# Mainboard.net
KiCad netlist of a schematic drawn in Altium Designer
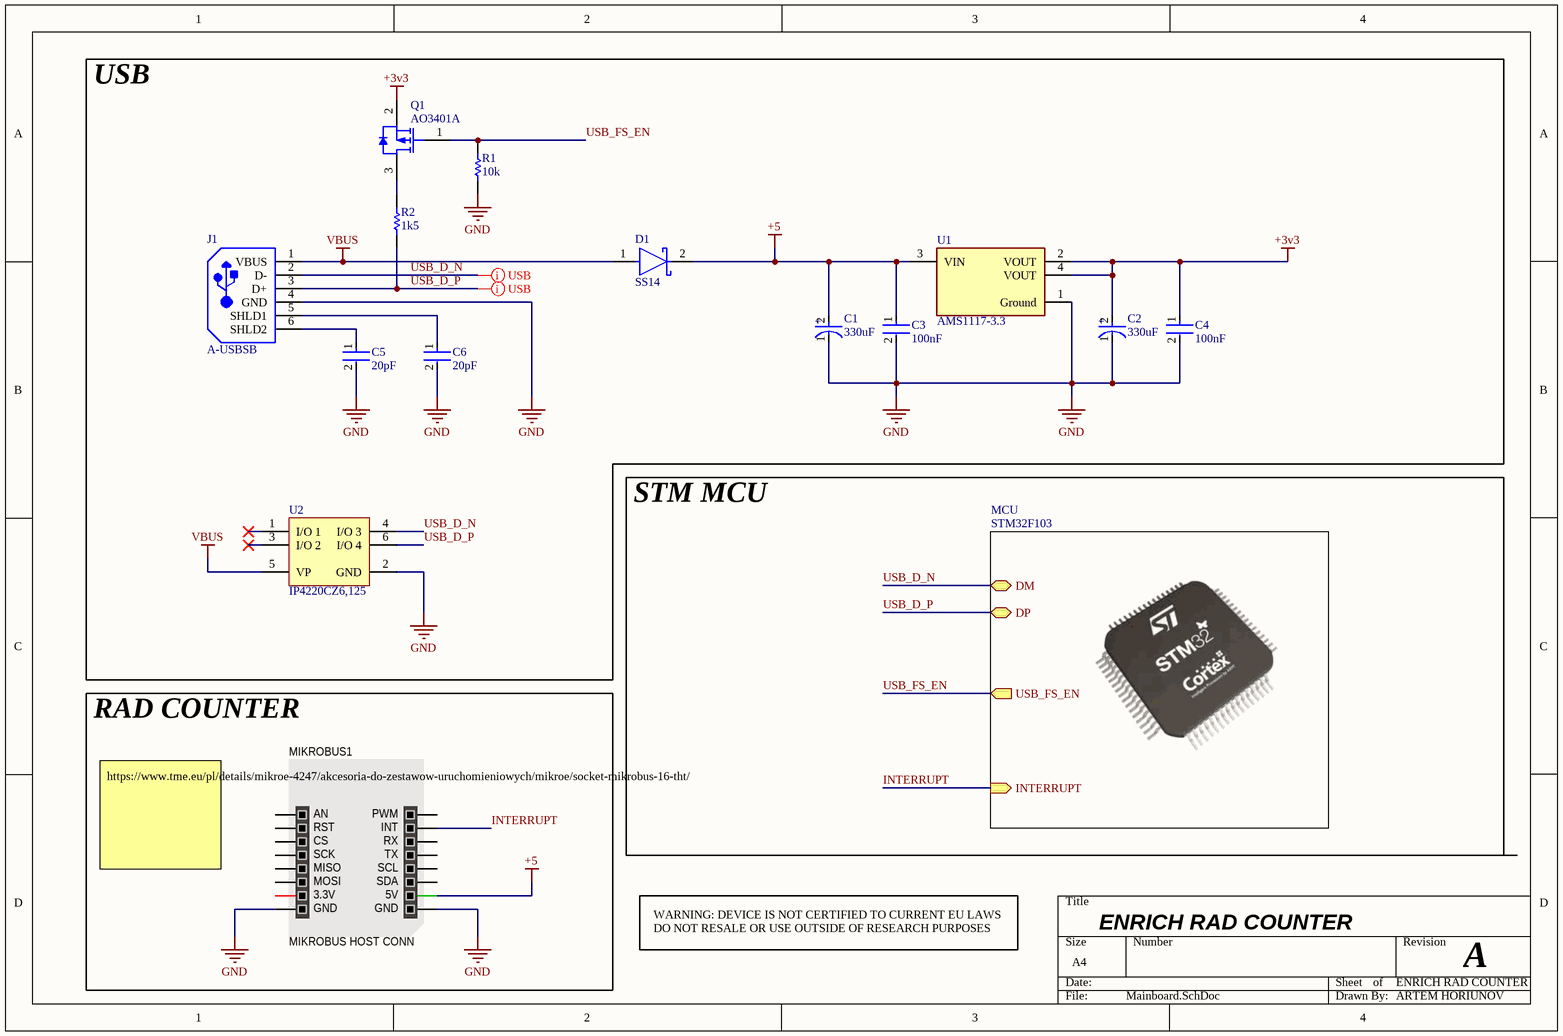
[diagram p0: Mainboard.SchDoc]

(export (version "E")
  (design (tool "Eeschema 10.0.6"))
  (components
    (comp (ref "C1")
      (value "330uF")
      (footprint "FP-OS-CON-SMT-F12-MFG")
      (description "Conductive Polymer Aluminum Solid Capacitors (OS-CON) 330uF ±20% 16V RADIAL SMT 10x12.6mm")
      (fields (field (name "TOLERANCE") "20%") (field (name "VOLTAGE") "16V"))
      (libsource (lib "Altium Content Vault") (part "a7907c86e72a156c28511143de7831b"))
    )
    (comp (ref "C2")
      (value "330uF")
      (footprint "FP-OS-CON-SMT-F12-MFG")
      (description "Conductive Polymer Aluminum Solid Capacitors (OS-CON) 330uF ±20% 16V RADIAL SMT 10x12.6mm")
      (fields (field (name "TOLERANCE") "20%") (field (name "VOLTAGE") "16V"))
      (libsource (lib "Altium Content Vault") (part "a7907c86e72a156c28511143de7831b"))
    )
    (comp (ref "C3")
      (value "100nF")
      (footprint "FP-C0402-BB-MFG")
      (description "CAP CER 0.1UF 10V X5R 0402")
      (fields (field (name "MANUFACTURER") "Kemet") (field (name "TOLERANCE") "0.1"))
      (libsource (lib "Altium Content Vault") (part "b4654b650e69147ec39a6b967a45e02"))
    )
    (comp (ref "C4")
      (value "100nF")
      (footprint "FP-C0402-BB-MFG")
      (description "CAP CER 0.1UF 10V X5R 0402")
      (fields (field (name "MANUFACTURER") "Kemet") (field (name "TOLERANCE") "0.1"))
      (libsource (lib "Altium Content Vault") (part "b4654b650e69147ec39a6b967a45e02"))
    )
    (comp (ref "C5")
      (value "20pF")
      (footprint "FP-C0603C-CF-MFG")
      (description "CAP CER 20PF 50V 5% NP0 0603")
      (fields
        (field (name "MANUFACTURER PART NUMBER") "C0603C200J5GACTU")
        (field (name "MANUFACTURER") "KEMET")
      )
      (libsource (lib "Altium Content Vault") (part "b4654b650e69147ec39a6b967a45e02"))
    )
    (comp (ref "C6")
      (value "20pF")
      (footprint "FP-C0603C-CF-MFG")
      (description "CAP CER 20PF 50V 5% NP0 0603")
      (fields
        (field (name "MANUFACTURER PART NUMBER") "C0603C200J5GACTU")
        (field (name "MANUFACTURER") "KEMET")
      )
      (libsource (lib "Altium Content Vault") (part "b4654b650e69147ec39a6b967a45e02"))
    )
    (comp (ref "D1")
      (value "SS14")
      (footprint "FP-403AE-MFG")
      (description "DIODE SCHOTTKY 40V 1A SMA")
      (fields
        (field (name "MANUFACTURER") "ON Semiconductor")
        (field (name "OCTOPART") "https://octopart.com/ss14-on+semiconductor-29205033")
      )
      (libsource (lib "Altium Content Vault") (part "360ad2f4ac25a952324d13796385471"))
    )
    (comp (ref "J1")
      (value "A-USBSB")
      (footprint "ASSM-A-USBSB-4_V")
      (description "Connector Receptacle, USB Type B, Right Angle, -20 to 85 degC, 4-Pin THD, RoHS, Tray")
      (fields (field (name "MANUFACTURER") "ASSMANN WSW"))
      (libsource (lib "Altium Content Vault") (part "USB-4-2SHLD"))
    )
    (comp (ref "MIKROBUS1")
      (value "MIKROBUS HOST CONN")
      (footprint "MIKROBUS HOST CONN 8gen TH")
      (libsource (lib "SOCKET mikroBUS 16 TH") (part "MIKROBUS HOST CONN"))
    )
    (comp (ref "Q1")
      (value "AO3401A")
      (footprint "AO-SOT-23-3L_V")
      (description "P-Channel MOSFET, 30 V, 4 A, -55 to 150 degC, 3-Pin SOT-23-3L, RoHS, Tape and Reel")
      (fields (field (name "MANUFACTURER") "Alpha and Omega"))
      (libsource (lib "Altium Content Vault") (part "PEMOS-GSD-3"))
    )
    (comp (ref "R1")
      (value "10k")
      (footprint "RESC1609X50X30NL8T20")
      (description "Chip Resistor, 10 KOhm, +/- 1%, 100 mW, -55 to 155 degC, 0603 (1608 Metric), RoHS, Tape and Reel")
      (fields (field (name "MANUFACTURER") "Vishay Semiconductor"))
      (libsource (lib "Altium Content Vault") (part "RES-2"))
    )
    (comp (ref "R2")
      (value "1k5")
      (footprint "RESC1608X55X30ML15T15")
      (fields (field (name "PART NUMBER") "ERJ-3EKF1501V") (field (name "MANUFACTURER") "Panasonic"))
      (libsource (lib "Altium Content Vault") (part "RES"))
    )
    (comp (ref "U1")
      (value "AMS1117-3.3")
      (footprint "FP-AMS1117-IPC_C")
      (description "LDO Voltage Regulators 1A, 3.3V")
      (fields
        (field (name "OCTOPART") "https://octopart.com/ams1117-3.3-advanced+monolithic+systems-25899300")
        (field (name "MANUFACTURER") "Advanced Monolithic Systems")
      )
      (libsource (lib "Altium Content Vault") (part "8bdbb5f8e77002000e30dd2845d0354"))
    )
    (comp (ref "U2")
      (value "IP4220CZ6,125")
      (footprint "NXP-SOT457_L")
      (fields (field (name "PARTNUMBER") "IP4220CZ6") (field (name "MANUFACTURER") "NXP Semiconductors"))
      (libsource (lib "Altium Content Vault") (part "NXP-IP4220CZ6-6"))
    )
  )
  (nets
    (net (code "1") (name "+3v3") (class "Default")
      (node (ref "C2") (pin "2") (pinfunction "A_2") (pintype "passive"))
      (node (ref "C4") (pin "1") (pinfunction "1_1") (pintype "passive"))
      (node (ref "Q1") (pin "2") (pinfunction "SOURCE_2") (pintype "passive"))
      (node (ref "U1") (pin "2") (pinfunction "VOUT_2") (pintype "passive"))
      (node (ref "U1") (pin "4") (pinfunction "VOUT_4") (pintype "passive"))
    )
    (net (code "2") (name "+5") (class "Default")
      (node (ref "C1") (pin "2") (pinfunction "A_2") (pintype "passive"))
      (node (ref "C3") (pin "1") (pinfunction "1_1") (pintype "passive"))
      (node (ref "D1") (pin "2") (pinfunction "C_2") (pintype "passive"))
      (node (ref "MIKROBUS1") (pin "10") (pinfunction "5V_10") (pintype "passive"))
      (node (ref "U1") (pin "3") (pinfunction "VIN_3") (pintype "power_in"))
    )
    (net (code "3") (name "/INTERRUPT") (class "Default")
      (node (ref "MIKROBUS1") (pin "15") (pinfunction "INT_15") (pintype "passive"))
    )
    (net (code "4") (name "/USB_D_N") (class "Default")
      (node (ref "J1") (pin "2") (pinfunction "D-_2") (pintype "passive"))
      (node (ref "U2") (pin "4") (pinfunction "I/O_3_4") (pintype "passive"))
    )
    (net (code "5") (name "/USB_D_P") (class "Default")
      (node (ref "J1") (pin "3") (pinfunction "D+_3") (pintype "passive"))
      (node (ref "R2") (pin "1") (pinfunction "1_1") (pintype "passive"))
      (node (ref "U2") (pin "6") (pinfunction "I/O_4_6") (pintype "passive"))
    )
    (net (code "6") (name "/USB_FS_EN") (class "Default")
      (node (ref "Q1") (pin "1") (pinfunction "GATE_1") (pintype "passive"))
      (node (ref "R1") (pin "1") (pinfunction "1_1") (pintype "passive"))
    )
    (net (code "7") (name "GND") (class "Default")
      (node (ref "C1") (pin "1") (pinfunction "C_1") (pintype "passive"))
      (node (ref "C2") (pin "1") (pinfunction "C_1") (pintype "passive"))
      (node (ref "C3") (pin "2") (pinfunction "2_2") (pintype "passive"))
      (node (ref "C4") (pin "2") (pinfunction "2_2") (pintype "passive"))
      (node (ref "C5") (pin "2") (pinfunction "2_2") (pintype "passive"))
      (node (ref "C6") (pin "2") (pinfunction "2_2") (pintype "passive"))
      (node (ref "J1") (pin "4") (pinfunction "GND_4") (pintype "passive"))
      (node (ref "MIKROBUS1") (pin "8") (pinfunction "GND_8") (pintype "passive"))
      (node (ref "MIKROBUS1") (pin "9") (pinfunction "GND_9") (pintype "passive"))
      (node (ref "R1") (pin "2") (pinfunction "2_2") (pintype "passive"))
      (node (ref "U1") (pin "1") (pinfunction "Ground_1") (pintype "power_in"))
      (node (ref "U2") (pin "2") (pinfunction "GND_2") (pintype "power_in"))
    )
    (net (code "8") (name "Net-(J1-SHLD1)") (class "Default")
      (node (ref "C6") (pin "1") (pinfunction "1_1") (pintype "passive"))
      (node (ref "J1") (pin "5") (pinfunction "SHLD1_5") (pintype "passive"))
    )
    (net (code "9") (name "Net-(J1-SHLD2)") (class "Default")
      (node (ref "C5") (pin "1") (pinfunction "1_1") (pintype "passive"))
      (node (ref "J1") (pin "6") (pinfunction "SHLD2_6") (pintype "passive"))
    )
    (net (code "10") (name "Net-(Q1-DRAIN)") (class "Default")
      (node (ref "Q1") (pin "3") (pinfunction "DRAIN_3") (pintype "passive"))
      (node (ref "R2") (pin "2") (pinfunction "2_2") (pintype "passive"))
    )
    (net (code "11") (name "VBUS") (class "Default")
      (node (ref "D1") (pin "1") (pinfunction "A_1") (pintype "passive"))
      (node (ref "J1") (pin "1") (pinfunction "VBUS_1") (pintype "passive"))
      (node (ref "U2") (pin "5") (pinfunction "VP_5") (pintype "power_in"))
    )
    (net (code "12") (name "unconnected-(MIKROBUS1-3.3V-Pad7)") (class "Default")
      (node (ref "MIKROBUS1") (pin "7") (pinfunction "3.3V_7") (pintype "passive"))
    )
    (net (code "13") (name "unconnected-(MIKROBUS1-AN-Pad1)") (class "Default")
      (node (ref "MIKROBUS1") (pin "1") (pinfunction "AN_1") (pintype "passive"))
    )
    (net (code "14") (name "unconnected-(MIKROBUS1-CS-Pad3)") (class "Default")
      (node (ref "MIKROBUS1") (pin "3") (pinfunction "CS_3") (pintype "passive"))
    )
    (net (code "15") (name "unconnected-(MIKROBUS1-MISO-Pad5)") (class "Default")
      (node (ref "MIKROBUS1") (pin "5") (pinfunction "MISO_5") (pintype "passive"))
    )
    (net (code "16") (name "unconnected-(MIKROBUS1-MOSI-Pad6)") (class "Default")
      (node (ref "MIKROBUS1") (pin "6") (pinfunction "MOSI_6") (pintype "passive"))
    )
    (net (code "17") (name "unconnected-(MIKROBUS1-PWM-Pad16)") (class "Default")
      (node (ref "MIKROBUS1") (pin "16") (pinfunction "PWM_16") (pintype "passive"))
    )
    (net (code "18") (name "unconnected-(MIKROBUS1-RST-Pad2)") (class "Default")
      (node (ref "MIKROBUS1") (pin "2") (pinfunction "RST_2") (pintype "passive"))
    )
    (net (code "19") (name "unconnected-(MIKROBUS1-RX-Pad14)") (class "Default")
      (node (ref "MIKROBUS1") (pin "14") (pinfunction "RX_14") (pintype "passive"))
    )
    (net (code "20") (name "unconnected-(MIKROBUS1-SCK-Pad4)") (class "Default")
      (node (ref "MIKROBUS1") (pin "4") (pinfunction "SCK_4") (pintype "passive"))
    )
    (net (code "21") (name "unconnected-(MIKROBUS1-SCL-Pad12)") (class "Default")
      (node (ref "MIKROBUS1") (pin "12") (pinfunction "SCL_12") (pintype "passive"))
    )
    (net (code "22") (name "unconnected-(MIKROBUS1-SDA-Pad11)") (class "Default")
      (node (ref "MIKROBUS1") (pin "11") (pinfunction "SDA_11") (pintype "passive"))
    )
    (net (code "23") (name "unconnected-(MIKROBUS1-TX-Pad13)") (class "Default")
      (node (ref "MIKROBUS1") (pin "13") (pinfunction "TX_13") (pintype "passive"))
    )
    (net (code "24") (name "unconnected-(U2-I{slash}O_1-Pad1)") (class "Default")
      (node (ref "U2") (pin "1") (pinfunction "I/O_1_1") (pintype "passive+no_connect"))
    )
    (net (code "25") (name "unconnected-(U2-I{slash}O_2-Pad3)") (class "Default")
      (node (ref "U2") (pin "3") (pinfunction "I/O_2_3") (pintype "passive+no_connect"))
    )
  )
)
